# FOC_Drive_2.net
KiCad netlist of a schematic drawn in Altium Designer
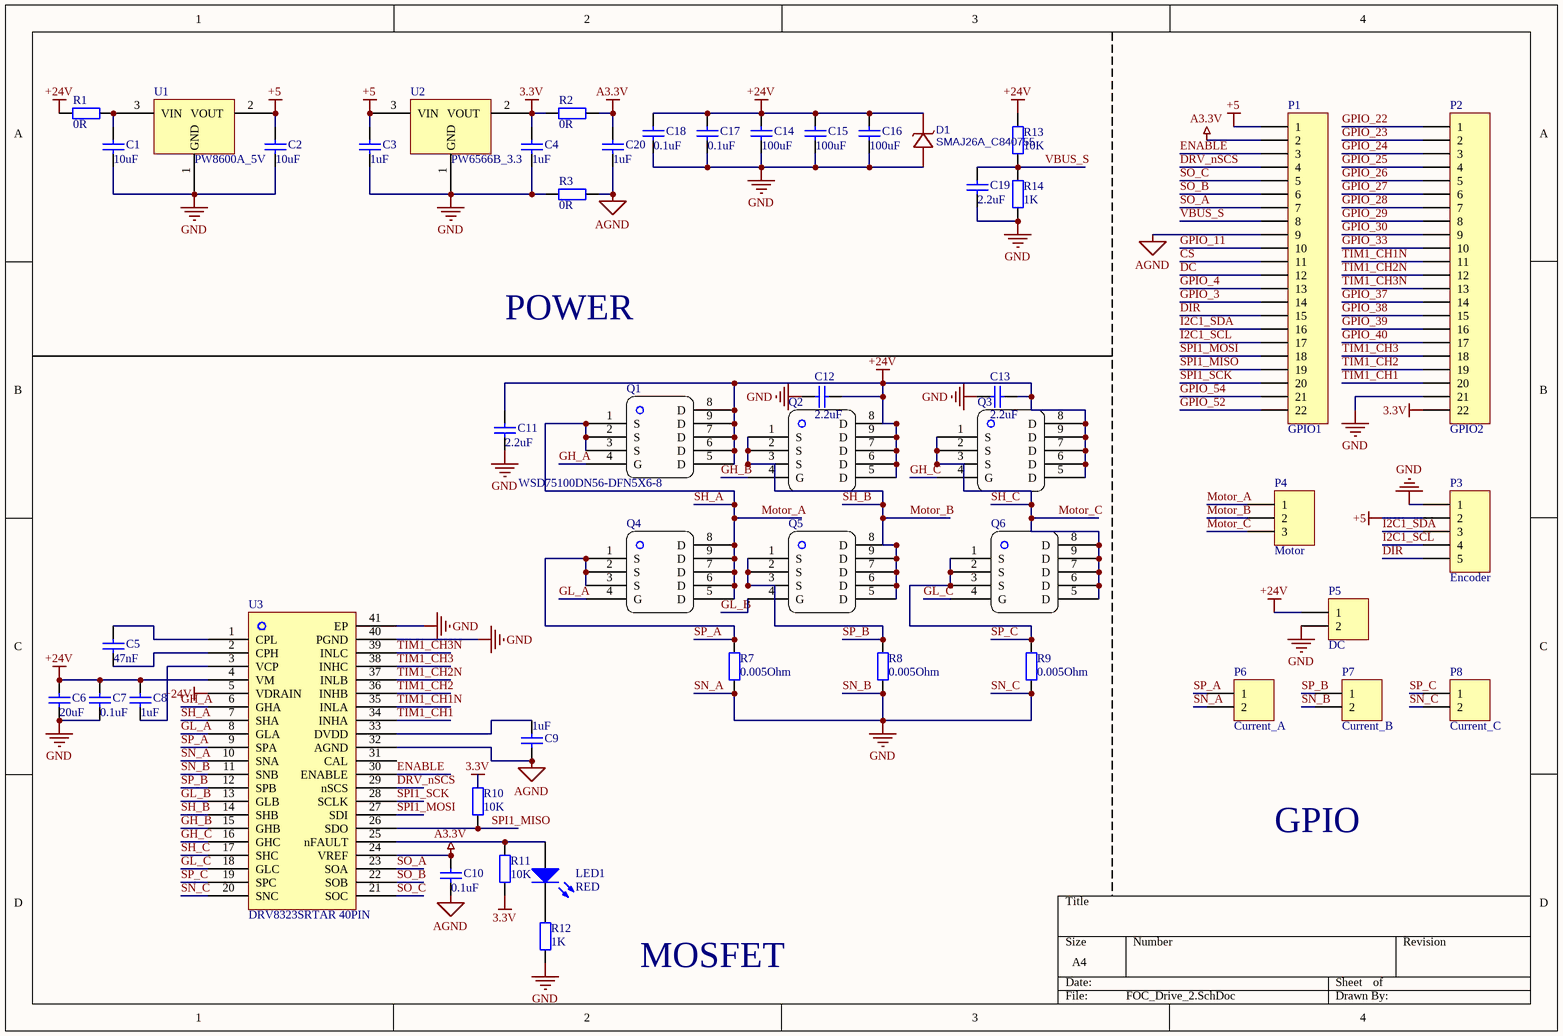
[diagram p0: FOC_Drive_2.SchDoc]

(export (version "E")
  (design (tool "Eeschema 10.0.6"))
  (components
    (comp (ref "C1")
      (value "10uF")
      (footprint "C0603")
      (description "Capacitor 50V")
      (fields (field (name "Comment") "Cap") (field (name "PUBLISHER") "Altium Limited"))
      (libsource (lib "Miscellaneous Devices") (part "Cap"))
    )
    (comp (ref "C2")
      (value "10uF")
      (footprint "C0603")
      (description "Capacitor 50V")
      (fields (field (name "Comment") "Cap") (field (name "PUBLISHER") "Altium Limited"))
      (libsource (lib "Miscellaneous Devices") (part "Cap"))
    )
    (comp (ref "C3")
      (value "1uF")
      (footprint "C0603")
      (description "Capacitor 50V")
      (fields (field (name "Comment") "Cap") (field (name "PUBLISHER") "Altium Limited"))
      (libsource (lib "Miscellaneous Devices") (part "Cap"))
    )
    (comp (ref "C4")
      (value "1uF")
      (footprint "C0603")
      (description "Capacitor 50V")
      (fields (field (name "Comment") "Cap") (field (name "PUBLISHER") "Altium Limited"))
      (libsource (lib "Miscellaneous Devices") (part "Cap"))
    )
    (comp (ref "C5")
      (value "47nF")
      (footprint "C0603")
      (description "Capacitor 50V")
      (fields (field (name "Comment") "Cap") (field (name "PUBLISHER") "Altium Limited"))
      (libsource (lib "Miscellaneous Devices") (part "Cap"))
    )
    (comp (ref "C6")
      (value "20uF")
      (footprint "C0603")
      (description "Capacitor 50V")
      (fields (field (name "Comment") "Cap") (field (name "PUBLISHER") "Altium Limited"))
      (libsource (lib "Miscellaneous Devices") (part "Cap"))
    )
    (comp (ref "C7")
      (value "0.1uF")
      (footprint "C0603")
      (description "Capacitor 50V")
      (fields (field (name "Comment") "Cap") (field (name "PUBLISHER") "Altium Limited"))
      (libsource (lib "Miscellaneous Devices") (part "Cap"))
    )
    (comp (ref "C8")
      (value "1uF")
      (footprint "C0603")
      (description "Capacitor 50V")
      (fields (field (name "Comment") "Cap") (field (name "PUBLISHER") "Altium Limited"))
      (libsource (lib "Miscellaneous Devices") (part "Cap"))
    )
    (comp (ref "C9")
      (value "1uF")
      (footprint "C0603")
      (description "Capacitor 50V")
      (fields (field (name "Comment") "Cap") (field (name "PUBLISHER") "Altium Limited"))
      (libsource (lib "Miscellaneous Devices") (part "Cap"))
    )
    (comp (ref "C10")
      (value "0.1uF")
      (footprint "C0603")
      (description "Capacitor 50V")
      (fields (field (name "Comment") "Cap") (field (name "PUBLISHER") "Altium Limited"))
      (libsource (lib "Miscellaneous Devices") (part "Cap"))
    )
    (comp (ref "C11")
      (value "2.2uF")
      (footprint "C0603")
      (description "Capacitor 50V")
      (fields (field (name "Comment") "Cap") (field (name "PUBLISHER") "Altium Limited"))
      (libsource (lib "Miscellaneous Devices") (part "Cap"))
    )
    (comp (ref "C12")
      (value "2.2uF")
      (footprint "C0603")
      (description "Capacitor 50V")
      (fields (field (name "Comment") "Cap") (field (name "PUBLISHER") "Altium Limited"))
      (libsource (lib "Miscellaneous Devices") (part "Cap"))
    )
    (comp (ref "C13")
      (value "2.2uF")
      (footprint "C0603")
      (description "Capacitor 50V")
      (fields (field (name "Comment") "Cap") (field (name "PUBLISHER") "Altium Limited"))
      (libsource (lib "Miscellaneous Devices") (part "Cap"))
    )
    (comp (ref "C14")
      (value "100uF")
      (footprint "C1206")
      (description "Capacitor 50V")
      (fields (field (name "Comment") "Cap") (field (name "PUBLISHER") "Altium Limited"))
      (libsource (lib "Miscellaneous Devices") (part "Cap"))
    )
    (comp (ref "C15")
      (value "100uF")
      (footprint "C1206")
      (description "Capacitor 50V")
      (fields (field (name "Comment") "Cap") (field (name "PUBLISHER") "Altium Limited"))
      (libsource (lib "Miscellaneous Devices") (part "Cap"))
    )
    (comp (ref "C16")
      (value "100uF")
      (footprint "C1206")
      (description "Capacitor 50V")
      (fields (field (name "Comment") "Cap") (field (name "PUBLISHER") "Altium Limited"))
      (libsource (lib "Miscellaneous Devices") (part "Cap"))
    )
    (comp (ref "C17")
      (value "0.1uF")
      (footprint "C0805")
      (description "Capacitor 50V")
      (fields (field (name "Comment") "Cap") (field (name "PUBLISHER") "Altium Limited"))
      (libsource (lib "Miscellaneous Devices") (part "Cap"))
    )
    (comp (ref "C18")
      (value "0.1uF")
      (footprint "C0805")
      (description "Capacitor 50V")
      (fields (field (name "Comment") "Cap") (field (name "PUBLISHER") "Altium Limited"))
      (libsource (lib "Miscellaneous Devices") (part "Cap"))
    )
    (comp (ref "C19")
      (value "2.2uF")
      (footprint "C0603")
      (description "Capacitor 50V")
      (fields (field (name "Comment") "Cap") (field (name "PUBLISHER") "Altium Limited"))
      (libsource (lib "Miscellaneous Devices") (part "Cap"))
    )
    (comp (ref "C20")
      (value "1uF")
      (footprint "C0603")
      (description "Capacitor 50V")
      (fields (field (name "Comment") "Cap") (field (name "PUBLISHER") "Altium Limited"))
      (libsource (lib "Miscellaneous Devices") (part "Cap"))
    )
    (comp (ref "D1")
      (value "SMAJ26A_C840755")
      (footprint "SMAJ26A-SMA_L4.3-W2.6-LS5.1-RD")
      (fields
        (field (name "BOM_SUPPLIER PART") "C840755")
        (field (name "BOM_MANUFACTURER PART") "SMAJ26A")
        (field (name "CONTRIBUTOR") "LCSC")
      )
      (libsource (lib "Schlib1") (part "SMAJ26A_C840755"))
    )
    (comp (ref "LED1")
      (value "RED")
      (footprint "0402-A")
      (description "Typical RED, GREEN, YELLOW, AMBER GaAs LED")
      (fields (field (name "PUBLISHER") "Altium Limited"))
      (libsource (lib "Miscellaneous Devices") (part "LED2"))
    )
    (comp (ref "P1")
      (value "GPIO1")
      (footprint "HDR1X22")
      (description "Header, 22-Pin")
      (fields (field (name "PUBLISHER") "Altium Limited"))
      (libsource (lib "Miscellaneous Connectors") (part "Header 22"))
    )
    (comp (ref "P2")
      (value "GPIO2")
      (footprint "HDR1X22")
      (description "Header, 22-Pin")
      (fields (field (name "PUBLISHER") "Altium Limited"))
      (libsource (lib "Miscellaneous Connectors") (part "Header 22"))
    )
    (comp (ref "P3")
      (value "Encoder")
      (footprint "CONN-SMD_5P-P2.00_HX20007-5AWB")
      (description "Header, 5-Pin")
      (fields (field (name "PUBLISHER") "Altium Limited"))
      (libsource (lib "Miscellaneous Connectors") (part "Header 5"))
    )
    (comp (ref "P4")
      (value "Motor")
      (footprint "CONN-TH_3P-P5.00_KF301-5.0-3P")
      (description "Header, 3-Pin")
      (fields (field (name "PUBLISHER") "Altium Limited"))
      (libsource (lib "Miscellaneous Connectors") (part "Header 3"))
    )
    (comp (ref "P5")
      (value "DC")
      (footprint "CONN-TH_P5.00_KF301-5.0-2P")
      (description "Header, 2-Pin")
      (fields (field (name "PUBLISHER") "Altium Limited"))
      (libsource (lib "Miscellaneous Connectors") (part "Header 2"))
    )
    (comp (ref "P6")
      (value "Current_A")
      (footprint "HDR1X2")
      (description "Header, 2-Pin")
      (fields (field (name "PUBLISHER") "Altium Limited"))
      (libsource (lib "Miscellaneous Connectors") (part "Header 2"))
    )
    (comp (ref "P7")
      (value "Current_B")
      (footprint "HDR1X2")
      (description "Header, 2-Pin")
      (fields (field (name "PUBLISHER") "Altium Limited"))
      (libsource (lib "Miscellaneous Connectors") (part "Header 2"))
    )
    (comp (ref "P8")
      (value "Current_C")
      (footprint "HDR1X2")
      (description "Header, 2-Pin")
      (fields (field (name "PUBLISHER") "Altium Limited"))
      (libsource (lib "Miscellaneous Connectors") (part "Header 2"))
    )
    (comp (ref "Q1")
      (value "WSD75100DN56-DFN5X6-8")
      (footprint "WSD75100DN56_DFN-8_L5.8-W4.9-P1.27-LS6.1-BL")
      (libsource (lib "Schlib1") (part "WSD75100DN56-DFN5X6-8"))
    )
    (comp (ref "Q2")
      (value "WSD75100DN56-DFN5X6-8")
      (footprint "WSD75100DN56_DFN-8_L5.8-W4.9-P1.27-LS6.1-BL")
      (libsource (lib "Schlib1") (part "WSD75100DN56-DFN5X6-8"))
    )
    (comp (ref "Q3")
      (value "WSD75100DN56-DFN5X6-8")
      (footprint "WSD75100DN56_DFN-8_L5.8-W4.9-P1.27-LS6.1-BL")
      (libsource (lib "Schlib1") (part "WSD75100DN56-DFN5X6-8"))
    )
    (comp (ref "Q4")
      (value "WSD75100DN56-DFN5X6-8")
      (footprint "WSD75100DN56_DFN-8_L5.8-W4.9-P1.27-LS6.1-BL")
      (libsource (lib "Schlib1") (part "WSD75100DN56-DFN5X6-8"))
    )
    (comp (ref "Q5")
      (value "WSD75100DN56-DFN5X6-8")
      (footprint "WSD75100DN56_DFN-8_L5.8-W4.9-P1.27-LS6.1-BL")
      (libsource (lib "Schlib1") (part "WSD75100DN56-DFN5X6-8"))
    )
    (comp (ref "Q6")
      (value "WSD75100DN56-DFN5X6-8")
      (footprint "WSD75100DN56_DFN-8_L5.8-W4.9-P1.27-LS6.1-BL")
      (libsource (lib "Schlib1") (part "WSD75100DN56-DFN5X6-8"))
    )
    (comp (ref "R1")
      (value "0R")
      (footprint "R0603")
      (description "Resistor")
      (fields (field (name "PUBLISHER") "Altium Limited"))
      (libsource (lib "") (part "Res2_1"))
    )
    (comp (ref "R2")
      (value "0R")
      (footprint "R0603")
      (description "Resistor")
      (fields (field (name "PUBLISHER") "Altium Limited"))
      (libsource (lib "") (part "Res2_1"))
    )
    (comp (ref "R3")
      (value "0R")
      (footprint "R0603")
      (description "Resistor")
      (fields (field (name "PUBLISHER") "Altium Limited"))
      (libsource (lib "") (part "Res2_1"))
    )
    (comp (ref "R7")
      (value "0.005Ohm")
      (footprint "R2512")
      (description "Resistor")
      (fields (field (name "PUBLISHER") "Altium Limited"))
      (libsource (lib "Miscellaneous Devices") (part "Res2"))
    )
    (comp (ref "R8")
      (value "0.005Ohm")
      (footprint "R2512")
      (description "Resistor")
      (fields (field (name "PUBLISHER") "Altium Limited"))
      (libsource (lib "Miscellaneous Devices") (part "Res2"))
    )
    (comp (ref "R9")
      (value "0.005Ohm")
      (footprint "R2512")
      (description "Resistor")
      (fields (field (name "PUBLISHER") "Altium Limited"))
      (libsource (lib "Miscellaneous Devices") (part "Res2"))
    )
    (comp (ref "R10")
      (value "10K")
      (footprint "R0603")
      (description "Resistor")
      (fields (field (name "PUBLISHER") "Altium Limited"))
      (libsource (lib "Miscellaneous Devices") (part "Res2"))
    )
    (comp (ref "R11")
      (value "10K")
      (footprint "R0603")
      (description "Resistor")
      (fields (field (name "PUBLISHER") "Altium Limited"))
      (libsource (lib "Miscellaneous Devices") (part "Res2"))
    )
    (comp (ref "R12")
      (value "1K")
      (footprint "R0603")
      (description "Resistor")
      (fields (field (name "PUBLISHER") "Altium Limited"))
      (libsource (lib "Miscellaneous Devices") (part "Res2"))
    )
    (comp (ref "R13")
      (value "10K")
      (footprint "R0603")
      (description "Resistor")
      (fields (field (name "PUBLISHER") "Altium Limited"))
      (libsource (lib "Miscellaneous Devices") (part "Res2"))
    )
    (comp (ref "R14")
      (value "1K")
      (footprint "R0603")
      (description "Resistor")
      (fields (field (name "PUBLISHER") "Altium Limited"))
      (libsource (lib "Miscellaneous Devices") (part "Res2"))
    )
    (comp (ref "U1")
      (value "PW8600A_5V")
      (footprint "SOT23-3_L2.9-W1.6-P1.90-LS2.8-BR")
      (libsource (lib "Schlib1") (part "AMS1117_3.3 SOT-89"))
    )
    (comp (ref "U2")
      (value "PW6566B_3.3")
      (footprint "SOT-23-3L_L2.9-W1.3-P1.90-LS2.4-BR")
      (libsource (lib "Schlib1") (part "AMS1117_3.3 SOT-89"))
    )
    (comp (ref "U3")
      (value "DRV8323SRTAR 40PIN")
      (footprint "DRV8323SRTAR WQFN-40_L6.0-W6.0-P0.50-TL-EP4.5")
      (libsource (lib "Schlib1") (part "DRV8323SRTAR 40PIN"))
    )
  )
  (nets
    (net (code "1") (name "+5") (class "Default")
      (node (ref "C2") (pin "2") (pinfunction "2_2") (pintype "passive"))
      (node (ref "C3") (pin "2") (pinfunction "2_2") (pintype "passive"))
      (node (ref "P1") (pin "1") (pinfunction "1_1") (pintype "passive"))
      (node (ref "P3") (pin "2") (pinfunction "2_2") (pintype "passive"))
      (node (ref "U1") (pin "2") (pinfunction "VOUT_2") (pintype "passive"))
      (node (ref "U2") (pin "3") (pinfunction "VIN_3") (pintype "passive"))
    )
    (net (code "2") (name "+24V") (class "Default")
      (node (ref "C11") (pin "2") (pinfunction "2_2") (pintype "passive"))
      (node (ref "C12") (pin "1") (pinfunction "1_1") (pintype "passive"))
      (node (ref "C13") (pin "1") (pinfunction "1_1") (pintype "passive"))
      (node (ref "C14") (pin "2") (pinfunction "2_2") (pintype "passive"))
      (node (ref "C15") (pin "2") (pinfunction "2_2") (pintype "passive"))
      (node (ref "C16") (pin "2") (pinfunction "2_2") (pintype "passive"))
      (node (ref "C17") (pin "2") (pinfunction "2_2") (pintype "passive"))
      (node (ref "C18") (pin "2") (pinfunction "2_2") (pintype "passive"))
      (node (ref "C6") (pin "2") (pinfunction "2_2") (pintype "passive"))
      (node (ref "C7") (pin "2") (pinfunction "2_2") (pintype "passive"))
      (node (ref "C8") (pin "2") (pinfunction "2_2") (pintype "passive"))
      (node (ref "D1") (pin "1") (pinfunction "C_1") (pintype "passive"))
      (node (ref "P5") (pin "1") (pinfunction "1_1") (pintype "passive"))
      (node (ref "Q1") (pin "5") (pinfunction "D_5") (pintype "passive"))
      (node (ref "Q1") (pin "6") (pinfunction "D_6") (pintype "passive"))
      (node (ref "Q1") (pin "7") (pinfunction "D_7") (pintype "passive"))
      (node (ref "Q1") (pin "8") (pinfunction "D_8") (pintype "passive"))
      (node (ref "Q1") (pin "9") (pinfunction "D_9") (pintype "passive"))
      (node (ref "Q2") (pin "5") (pinfunction "D_5") (pintype "passive"))
      (node (ref "Q2") (pin "6") (pinfunction "D_6") (pintype "passive"))
      (node (ref "Q2") (pin "7") (pinfunction "D_7") (pintype "passive"))
      (node (ref "Q2") (pin "8") (pinfunction "D_8") (pintype "passive"))
      (node (ref "Q2") (pin "9") (pinfunction "D_9") (pintype "passive"))
      (node (ref "Q3") (pin "5") (pinfunction "D_5") (pintype "passive"))
      (node (ref "Q3") (pin "6") (pinfunction "D_6") (pintype "passive"))
      (node (ref "Q3") (pin "7") (pinfunction "D_7") (pintype "passive"))
      (node (ref "Q3") (pin "8") (pinfunction "D_8") (pintype "passive"))
      (node (ref "Q3") (pin "9") (pinfunction "D_9") (pintype "passive"))
      (node (ref "R1") (pin "1") (pinfunction "1_1") (pintype "passive"))
      (node (ref "R13") (pin "2") (pinfunction "2_2") (pintype "passive"))
      (node (ref "U3") (pin "4") (pinfunction "VM_4") (pintype "passive"))
      (node (ref "U3") (pin "5") (pinfunction "VDRAIN_5") (pintype "passive"))
    )
    (net (code "3") (name "/CS") (class "Default")
      (node (ref "P1") (pin "11") (pinfunction "11_11") (pintype "passive"))
    )
    (net (code "4") (name "/DC") (class "Default")
      (node (ref "P1") (pin "12") (pinfunction "12_12") (pintype "passive"))
    )
    (net (code "5") (name "/DIR") (class "Default")
      (node (ref "P1") (pin "15") (pinfunction "15_15") (pintype "passive"))
      (node (ref "P3") (pin "5") (pinfunction "5_5") (pintype "passive"))
    )
    (net (code "6") (name "/DRV_nSCS") (class "Default")
      (node (ref "P1") (pin "4") (pinfunction "4_4") (pintype "passive"))
      (node (ref "U3") (pin "29") (pinfunction "nSCS_29") (pintype "passive"))
    )
    (net (code "7") (name "/ENABLE") (class "Default")
      (node (ref "P1") (pin "3") (pinfunction "3_3") (pintype "passive"))
      (node (ref "U3") (pin "30") (pinfunction "ENABLE_30") (pintype "passive"))
    )
    (net (code "8") (name "/GH_A") (class "Default")
      (node (ref "Q1") (pin "4") (pinfunction "G_4") (pintype "passive"))
      (node (ref "U3") (pin "6") (pinfunction "GHA_6") (pintype "passive"))
    )
    (net (code "9") (name "/GH_B") (class "Default")
      (node (ref "Q2") (pin "4") (pinfunction "G_4") (pintype "passive"))
      (node (ref "U3") (pin "15") (pinfunction "GHB_15") (pintype "passive"))
    )
    (net (code "10") (name "/GH_C") (class "Default")
      (node (ref "Q3") (pin "4") (pinfunction "G_4") (pintype "passive"))
      (node (ref "U3") (pin "16") (pinfunction "GHC_16") (pintype "passive"))
    )
    (net (code "11") (name "/GL_A") (class "Default")
      (node (ref "Q4") (pin "4") (pinfunction "G_4") (pintype "passive"))
      (node (ref "U3") (pin "8") (pinfunction "GLA_8") (pintype "passive"))
    )
    (net (code "12") (name "/GL_B") (class "Default")
      (node (ref "Q5") (pin "4") (pinfunction "G_4") (pintype "passive"))
      (node (ref "U3") (pin "13") (pinfunction "GLB_13") (pintype "passive"))
    )
    (net (code "13") (name "/GL_C") (class "Default")
      (node (ref "Q6") (pin "4") (pinfunction "G_4") (pintype "passive"))
      (node (ref "U3") (pin "18") (pinfunction "GLC_18") (pintype "passive"))
    )
    (net (code "14") (name "/GPIO_3") (class "Default")
      (node (ref "P1") (pin "14") (pinfunction "14_14") (pintype "passive"))
    )
    (net (code "15") (name "/GPIO_4") (class "Default")
      (node (ref "P1") (pin "13") (pinfunction "13_13") (pintype "passive"))
    )
    (net (code "16") (name "/GPIO_11") (class "Default")
      (node (ref "P1") (pin "10") (pinfunction "10_10") (pintype "passive"))
    )
    (net (code "17") (name "/GPIO_22") (class "Default")
      (node (ref "P2") (pin "1") (pinfunction "1_1") (pintype "passive"))
    )
    (net (code "18") (name "/GPIO_23") (class "Default")
      (node (ref "P2") (pin "2") (pinfunction "2_2") (pintype "passive"))
    )
    (net (code "19") (name "/GPIO_24") (class "Default")
      (node (ref "P2") (pin "3") (pinfunction "3_3") (pintype "passive"))
    )
    (net (code "20") (name "/GPIO_25") (class "Default")
      (node (ref "P2") (pin "4") (pinfunction "4_4") (pintype "passive"))
    )
    (net (code "21") (name "/GPIO_26") (class "Default")
      (node (ref "P2") (pin "5") (pinfunction "5_5") (pintype "passive"))
    )
    (net (code "22") (name "/GPIO_27") (class "Default")
      (node (ref "P2") (pin "6") (pinfunction "6_6") (pintype "passive"))
    )
    (net (code "23") (name "/GPIO_28") (class "Default")
      (node (ref "P2") (pin "7") (pinfunction "7_7") (pintype "passive"))
    )
    (net (code "24") (name "/GPIO_29") (class "Default")
      (node (ref "P2") (pin "8") (pinfunction "8_8") (pintype "passive"))
    )
    (net (code "25") (name "/GPIO_30") (class "Default")
      (node (ref "P2") (pin "9") (pinfunction "9_9") (pintype "passive"))
    )
    (net (code "26") (name "/GPIO_33") (class "Default")
      (node (ref "P2") (pin "10") (pinfunction "10_10") (pintype "passive"))
    )
    (net (code "27") (name "/GPIO_37") (class "Default")
      (node (ref "P2") (pin "14") (pinfunction "14_14") (pintype "passive"))
    )
    (net (code "28") (name "/GPIO_38") (class "Default")
      (node (ref "P2") (pin "15") (pinfunction "15_15") (pintype "passive"))
    )
    (net (code "29") (name "/GPIO_39") (class "Default")
      (node (ref "P2") (pin "16") (pinfunction "16_16") (pintype "passive"))
    )
    (net (code "30") (name "/GPIO_40") (class "Default")
      (node (ref "P2") (pin "17") (pinfunction "17_17") (pintype "passive"))
    )
    (net (code "31") (name "/GPIO_52") (class "Default")
      (node (ref "P1") (pin "22") (pinfunction "22_22") (pintype "passive"))
    )
    (net (code "32") (name "/GPIO_54") (class "Default")
      (node (ref "P1") (pin "21") (pinfunction "21_21") (pintype "passive"))
    )
    (net (code "33") (name "/I2C1_SCL") (class "Default")
      (node (ref "P1") (pin "17") (pinfunction "17_17") (pintype "passive"))
      (node (ref "P3") (pin "4") (pinfunction "4_4") (pintype "passive"))
    )
    (net (code "34") (name "/I2C1_SDA") (class "Default")
      (node (ref "P1") (pin "16") (pinfunction "16_16") (pintype "passive"))
      (node (ref "P3") (pin "3") (pinfunction "3_3") (pintype "passive"))
    )
    (net (code "35") (name "/Motor_A") (class "Default")
      (node (ref "P4") (pin "1") (pinfunction "1_1") (pintype "passive"))
      (node (ref "Q1") (pin "1") (pinfunction "S_1") (pintype "passive"))
      (node (ref "Q1") (pin "2") (pinfunction "S_2") (pintype "passive"))
      (node (ref "Q1") (pin "3") (pinfunction "S_3") (pintype "passive"))
      (node (ref "Q4") (pin "5") (pinfunction "D_5") (pintype "passive"))
      (node (ref "Q4") (pin "6") (pinfunction "D_6") (pintype "passive"))
      (node (ref "Q4") (pin "7") (pinfunction "D_7") (pintype "passive"))
      (node (ref "Q4") (pin "8") (pinfunction "D_8") (pintype "passive"))
      (node (ref "Q4") (pin "9") (pinfunction "D_9") (pintype "passive"))
      (node (ref "U3") (pin "7") (pinfunction "SHA_7") (pintype "passive"))
    )
    (net (code "36") (name "/Motor_B") (class "Default")
      (node (ref "P4") (pin "2") (pinfunction "2_2") (pintype "passive"))
      (node (ref "Q2") (pin "1") (pinfunction "S_1") (pintype "passive"))
      (node (ref "Q2") (pin "2") (pinfunction "S_2") (pintype "passive"))
      (node (ref "Q2") (pin "3") (pinfunction "S_3") (pintype "passive"))
      (node (ref "Q5") (pin "5") (pinfunction "D_5") (pintype "passive"))
      (node (ref "Q5") (pin "6") (pinfunction "D_6") (pintype "passive"))
      (node (ref "Q5") (pin "7") (pinfunction "D_7") (pintype "passive"))
      (node (ref "Q5") (pin "8") (pinfunction "D_8") (pintype "passive"))
      (node (ref "Q5") (pin "9") (pinfunction "D_9") (pintype "passive"))
      (node (ref "U3") (pin "14") (pinfunction "SHB_14") (pintype "passive"))
    )
    (net (code "37") (name "/Motor_C") (class "Default")
      (node (ref "P4") (pin "3") (pinfunction "3_3") (pintype "passive"))
      (node (ref "Q3") (pin "1") (pinfunction "S_1") (pintype "passive"))
      (node (ref "Q3") (pin "2") (pinfunction "S_2") (pintype "passive"))
      (node (ref "Q3") (pin "3") (pinfunction "S_3") (pintype "passive"))
      (node (ref "Q6") (pin "5") (pinfunction "D_5") (pintype "passive"))
      (node (ref "Q6") (pin "6") (pinfunction "D_6") (pintype "passive"))
      (node (ref "Q6") (pin "7") (pinfunction "D_7") (pintype "passive"))
      (node (ref "Q6") (pin "8") (pinfunction "D_8") (pintype "passive"))
      (node (ref "Q6") (pin "9") (pinfunction "D_9") (pintype "passive"))
      (node (ref "U3") (pin "17") (pinfunction "SHC_17") (pintype "passive"))
    )
    (net (code "38") (name "/SO_A") (class "Default")
      (node (ref "P1") (pin "7") (pinfunction "7_7") (pintype "passive"))
      (node (ref "U3") (pin "23") (pinfunction "SOA_23") (pintype "passive"))
    )
    (net (code "39") (name "/SO_B") (class "Default")
      (node (ref "P1") (pin "6") (pinfunction "6_6") (pintype "passive"))
      (node (ref "U3") (pin "22") (pinfunction "SOB_22") (pintype "passive"))
    )
    (net (code "40") (name "/SO_C") (class "Default")
      (node (ref "P1") (pin "5") (pinfunction "5_5") (pintype "passive"))
      (node (ref "U3") (pin "21") (pinfunction "SOC_21") (pintype "passive"))
    )
    (net (code "41") (name "/SPI1_MISO") (class "Default")
      (node (ref "P1") (pin "19") (pinfunction "19_19") (pintype "passive"))
      (node (ref "R10") (pin "1") (pinfunction "1_1") (pintype "passive"))
      (node (ref "U3") (pin "26") (pinfunction "SDO_26") (pintype "passive"))
    )
    (net (code "42") (name "/SPI1_MOSI") (class "Default")
      (node (ref "P1") (pin "18") (pinfunction "18_18") (pintype "passive"))
      (node (ref "U3") (pin "27") (pinfunction "SDI_27") (pintype "passive"))
    )
    (net (code "43") (name "/SPI1_SCK") (class "Default")
      (node (ref "P1") (pin "20") (pinfunction "20_20") (pintype "passive"))
      (node (ref "U3") (pin "28") (pinfunction "SCLK_28") (pintype "passive"))
    )
    (net (code "44") (name "/SP_A") (class "Default")
      (node (ref "P6") (pin "1") (pinfunction "1_1") (pintype "passive"))
      (node (ref "Q4") (pin "1") (pinfunction "S_1") (pintype "passive"))
      (node (ref "Q4") (pin "2") (pinfunction "S_2") (pintype "passive"))
      (node (ref "Q4") (pin "3") (pinfunction "S_3") (pintype "passive"))
      (node (ref "R7") (pin "2") (pinfunction "2_2") (pintype "passive"))
      (node (ref "U3") (pin "9") (pinfunction "SPA_9") (pintype "passive"))
    )
    (net (code "45") (name "/SP_B") (class "Default")
      (node (ref "P7") (pin "1") (pinfunction "1_1") (pintype "passive"))
      (node (ref "Q5") (pin "1") (pinfunction "S_1") (pintype "passive"))
      (node (ref "Q5") (pin "2") (pinfunction "S_2") (pintype "passive"))
      (node (ref "Q5") (pin "3") (pinfunction "S_3") (pintype "passive"))
      (node (ref "R8") (pin "2") (pinfunction "2_2") (pintype "passive"))
      (node (ref "U3") (pin "12") (pinfunction "SPB_12") (pintype "passive"))
    )
    (net (code "46") (name "/SP_C") (class "Default")
      (node (ref "P8") (pin "1") (pinfunction "1_1") (pintype "passive"))
      (node (ref "Q6") (pin "1") (pinfunction "S_1") (pintype "passive"))
      (node (ref "Q6") (pin "2") (pinfunction "S_2") (pintype "passive"))
      (node (ref "Q6") (pin "3") (pinfunction "S_3") (pintype "passive"))
      (node (ref "R9") (pin "2") (pinfunction "2_2") (pintype "passive"))
      (node (ref "U3") (pin "19") (pinfunction "SPC_19") (pintype "passive"))
    )
    (net (code "47") (name "/TIM1_CH1") (class "Default")
      (node (ref "P2") (pin "20") (pinfunction "20_20") (pintype "passive"))
      (node (ref "U3") (pin "34") (pinfunction "INHA_34") (pintype "passive"))
    )
    (net (code "48") (name "/TIM1_CH1N") (class "Default")
      (node (ref "P2") (pin "11") (pinfunction "11_11") (pintype "passive"))
      (node (ref "U3") (pin "35") (pinfunction "INLA_35") (pintype "passive"))
    )
    (net (code "49") (name "/TIM1_CH2") (class "Default")
      (node (ref "P2") (pin "19") (pinfunction "19_19") (pintype "passive"))
      (node (ref "U3") (pin "36") (pinfunction "INHB_36") (pintype "passive"))
    )
    (net (code "50") (name "/TIM1_CH2N") (class "Default")
      (node (ref "P2") (pin "12") (pinfunction "12_12") (pintype "passive"))
      (node (ref "U3") (pin "37") (pinfunction "INLB_37") (pintype "passive"))
    )
    (net (code "51") (name "/TIM1_CH3") (class "Default")
      (node (ref "P2") (pin "18") (pinfunction "18_18") (pintype "passive"))
      (node (ref "U3") (pin "38") (pinfunction "INHC_38") (pintype "passive"))
    )
    (net (code "52") (name "/TIM1_CH3N") (class "Default")
      (node (ref "P2") (pin "13") (pinfunction "13_13") (pintype "passive"))
      (node (ref "U3") (pin "39") (pinfunction "INLC_39") (pintype "passive"))
    )
    (net (code "53") (name "/VBUS_S") (class "Default")
      (node (ref "C19") (pin "2") (pinfunction "2_2") (pintype "passive"))
      (node (ref "P1") (pin "8") (pinfunction "8_8") (pintype "passive"))
      (node (ref "R13") (pin "1") (pinfunction "1_1") (pintype "passive"))
      (node (ref "R14") (pin "2") (pinfunction "2_2") (pintype "passive"))
    )
    (net (code "54") (name "3.3V") (class "Default")
      (node (ref "C4") (pin "2") (pinfunction "2_2") (pintype "passive"))
      (node (ref "P2") (pin "22") (pinfunction "22_22") (pintype "passive"))
      (node (ref "R10") (pin "2") (pinfunction "2_2") (pintype "passive"))
      (node (ref "R11") (pin "1") (pinfunction "1_1") (pintype "passive"))
      (node (ref "R2") (pin "1") (pinfunction "1_1") (pintype "passive"))
      (node (ref "U2") (pin "2") (pinfunction "VOUT_2") (pintype "passive"))
    )
    (net (code "55") (name "A3.3V") (class "Default")
      (node (ref "C10") (pin "2") (pinfunction "2_2") (pintype "passive"))
      (node (ref "C20") (pin "2") (pinfunction "2_2") (pintype "passive"))
      (node (ref "P1") (pin "2") (pinfunction "2_2") (pintype "passive"))
      (node (ref "R2") (pin "2") (pinfunction "2_2") (pintype "passive"))
      (node (ref "U3") (pin "24") (pinfunction "VREF_24") (pintype "passive"))
    )
    (net (code "56") (name "AGND") (class "Default")
      (node (ref "C10") (pin "1") (pinfunction "1_1") (pintype "passive"))
      (node (ref "C20") (pin "1") (pinfunction "1_1") (pintype "passive"))
      (node (ref "C9") (pin "1") (pinfunction "1_1") (pintype "passive"))
      (node (ref "P1") (pin "9") (pinfunction "9_9") (pintype "passive"))
      (node (ref "R3") (pin "2") (pinfunction "2_2") (pintype "passive"))
      (node (ref "U3") (pin "32") (pinfunction "AGND_32") (pintype "passive"))
    )
    (net (code "57") (name "GND") (class "Default")
      (node (ref "C1") (pin "1") (pinfunction "1_1") (pintype "passive"))
      (node (ref "C11") (pin "1") (pinfunction "1_1") (pintype "passive"))
      (node (ref "C12") (pin "2") (pinfunction "2_2") (pintype "passive"))
      (node (ref "C13") (pin "2") (pinfunction "2_2") (pintype "passive"))
      (node (ref "C14") (pin "1") (pinfunction "1_1") (pintype "passive"))
      (node (ref "C15") (pin "1") (pinfunction "1_1") (pintype "passive"))
      (node (ref "C16") (pin "1") (pinfunction "1_1") (pintype "passive"))
      (node (ref "C17") (pin "1") (pinfunction "1_1") (pintype "passive"))
      (node (ref "C18") (pin "1") (pinfunction "1_1") (pintype "passive"))
      (node (ref "C19") (pin "1") (pinfunction "1_1") (pintype "passive"))
      (node (ref "C2") (pin "1") (pinfunction "1_1") (pintype "passive"))
      (node (ref "C3") (pin "1") (pinfunction "1_1") (pintype "passive"))
      (node (ref "C4") (pin "1") (pinfunction "1_1") (pintype "passive"))
      (node (ref "C6") (pin "1") (pinfunction "1_1") (pintype "passive"))
      (node (ref "C7") (pin "1") (pinfunction "1_1") (pintype "passive"))
      (node (ref "D1") (pin "2") (pinfunction "A_2") (pintype "passive"))
      (node (ref "P2") (pin "21") (pinfunction "21_21") (pintype "passive"))
      (node (ref "P3") (pin "1") (pinfunction "1_1") (pintype "passive"))
      (node (ref "P5") (pin "2") (pinfunction "2_2") (pintype "passive"))
      (node (ref "P6") (pin "2") (pinfunction "2_2") (pintype "passive"))
      (node (ref "P7") (pin "2") (pinfunction "2_2") (pintype "passive"))
      (node (ref "P8") (pin "2") (pinfunction "2_2") (pintype "passive"))
      (node (ref "R12") (pin "1") (pinfunction "1_1") (pintype "passive"))
      (node (ref "R14") (pin "1") (pinfunction "1_1") (pintype "passive"))
      (node (ref "R3") (pin "1") (pinfunction "1_1") (pintype "passive"))
      (node (ref "R7") (pin "1") (pinfunction "1_1") (pintype "passive"))
      (node (ref "R8") (pin "1") (pinfunction "1_1") (pintype "passive"))
      (node (ref "R9") (pin "1") (pinfunction "1_1") (pintype "passive"))
      (node (ref "U1") (pin "1") (pinfunction "GND_1") (pintype "passive"))
      (node (ref "U2") (pin "1") (pinfunction "GND_1") (pintype "passive"))
      (node (ref "U3") (pin "10") (pinfunction "SNA_10") (pintype "passive"))
      (node (ref "U3") (pin "11") (pinfunction "SNB_11") (pintype "passive"))
      (node (ref "U3") (pin "20") (pinfunction "SNC_20") (pintype "passive"))
      (node (ref "U3") (pin "40") (pinfunction "PGND_40") (pintype "passive"))
      (node (ref "U3") (pin "41") (pinfunction "EP_41") (pintype "passive"))
    )
    (net (code "58") (name "Net-(LED1-A)") (class "Default")
      (node (ref "LED1") (pin "1") (pinfunction "A_1") (pintype "passive"))
      (node (ref "R11") (pin "2") (pinfunction "2_2") (pintype "passive"))
      (node (ref "U3") (pin "25") (pinfunction "nFAULT_25") (pintype "passive"))
    )
    (net (code "59") (name "Net-(LED1-K)") (class "Default")
      (node (ref "LED1") (pin "2") (pinfunction "K_2") (pintype "passive"))
      (node (ref "R12") (pin "2") (pinfunction "2_2") (pintype "passive"))
    )
    (net (code "60") (name "Net-(U1-VIN)") (class "Default")
      (node (ref "C1") (pin "2") (pinfunction "2_2") (pintype "passive"))
      (node (ref "R1") (pin "2") (pinfunction "2_2") (pintype "passive"))
      (node (ref "U1") (pin "3") (pinfunction "VIN_3") (pintype "passive"))
    )
    (net (code "61") (name "Net-(U3-CPH)") (class "Default")
      (node (ref "C5") (pin "1") (pinfunction "1_1") (pintype "passive"))
      (node (ref "U3") (pin "2") (pinfunction "CPH_2") (pintype "passive"))
    )
    (net (code "62") (name "Net-(U3-CPL)") (class "Default")
      (node (ref "C5") (pin "2") (pinfunction "2_2") (pintype "passive"))
      (node (ref "U3") (pin "1") (pinfunction "CPL_1") (pintype "passive"))
    )
    (net (code "63") (name "Net-(U3-DVDD)") (class "Default")
      (node (ref "C9") (pin "2") (pinfunction "2_2") (pintype "passive"))
      (node (ref "U3") (pin "33") (pinfunction "DVDD_33") (pintype "passive"))
    )
    (net (code "64") (name "Net-(U3-VCP)") (class "Default")
      (node (ref "C8") (pin "1") (pinfunction "1_1") (pintype "passive"))
      (node (ref "U3") (pin "3") (pinfunction "VCP_3") (pintype "passive"))
    )
    (net (code "65") (name "unconnected-(U3-CAL-Pad31)") (class "Default")
      (node (ref "U3") (pin "31") (pinfunction "CAL_31") (pintype "passive"))
    )
  )
)
